# Acoustics_Board.net
KiCad netlist of a schematic drawn in Altium Designer
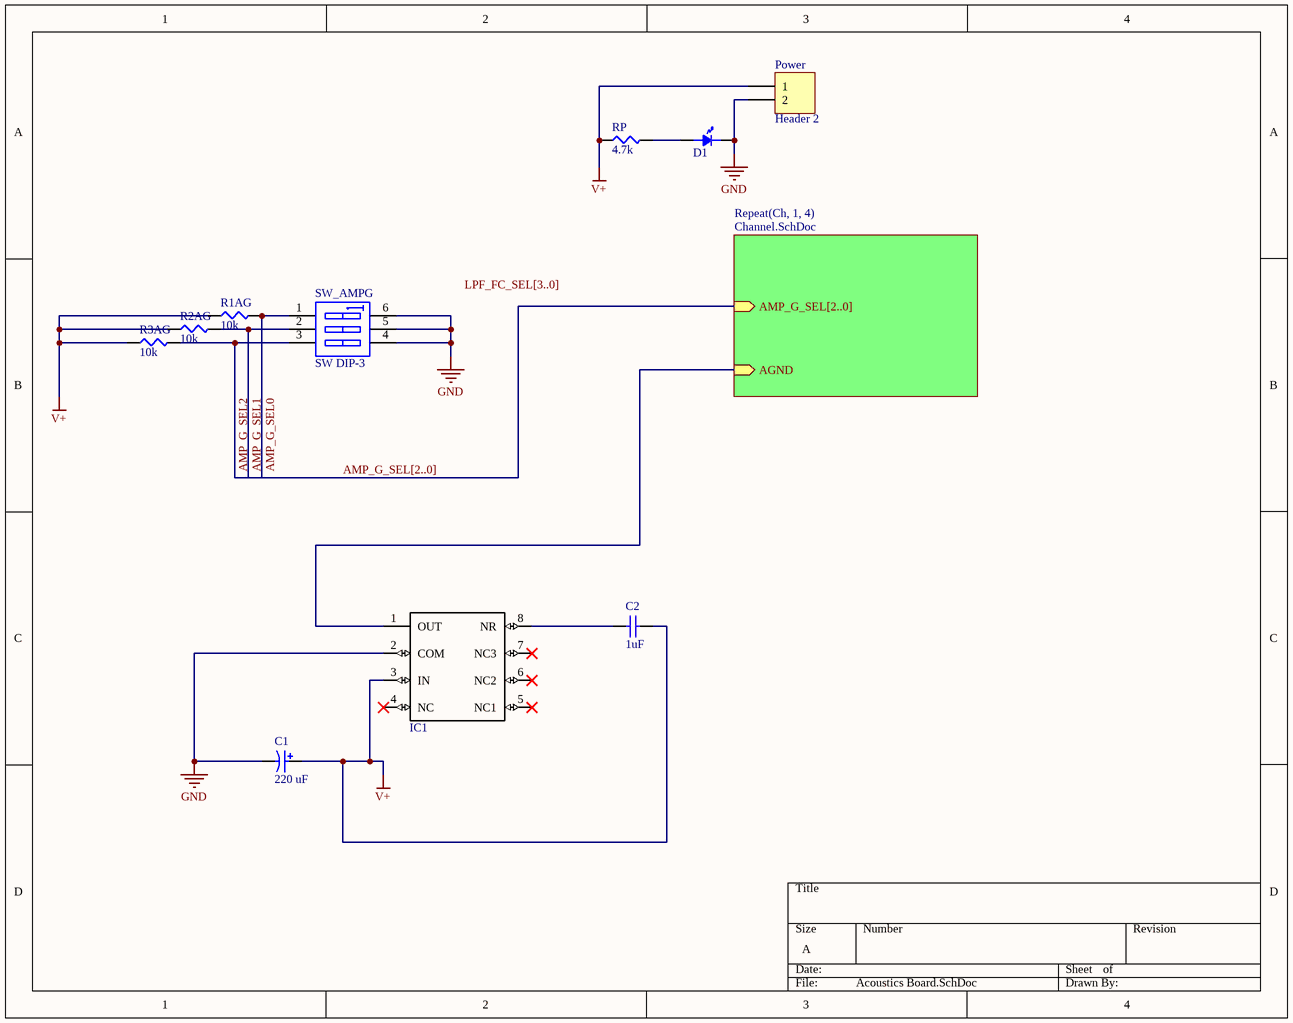
[diagram p0: Acoustics Board.SchDoc]

(export (version "E")
  (design (tool "Eeschema 10.0.6"))
  (components
    (comp (ref "C1")
      (value "220 uF")
      (footprint "PNSC-FK-V-H13_V")
      (fields (field (name "MANUFACTURER") "Panasonic"))
      (libsource (lib "Altium Content Vault") (part "CAP-P-2"))
    )
    (comp (ref "C2")
      (value "1uF")
      (footprint "C0805")
      (description "Unpolarized Capacitor")
      (fields (field (name "Comment") "Cap"))
      (libsource (lib "URC_Lib") (part "Cap"))
    )
    (comp (ref "D1") (value "LED") (footprint "LED0805") (libsource (lib "URC_Lib") (part "LED")))
    (comp (ref "IC1")
      (value "TLE2426")
      (footprint "SO8_M")
      (fields (field (name "MF") "Texas Instruments"))
      (libsource (lib "TLE2426") (part "TLE2426"))
    )
    (comp (ref "Power")
      (value "Header 2")
      (footprint "HDR1X2")
      (description "Header, 2-Pin")
      (fields (field (name "PUBLISHER") "Altium Limited"))
      (libsource (lib "Miscellaneous Connectors") (part "Header 2"))
    )
    (comp (ref "R1AG")
      (value "10k")
      (footprint "SMD-0805-RES")
      (description "RES SMD 10K OHM 1% 1/8W 0805")
      (fields
        (field (name "PART NUMBER") "ERJ-6ENF1002V")
        (field (name "DIGI-KEY PART NUMBER") "P10.0KCCT-ND")
      )
      (libsource (lib "Panasonic_ERJ_0805") (part "ERJ-6ENF1002V"))
    )
    (comp (ref "R2AG")
      (value "10k")
      (footprint "SMD-0805-RES")
      (description "RES SMD 10K OHM 1% 1/8W 0805")
      (fields
        (field (name "PART NUMBER") "ERJ-6ENF1002V")
        (field (name "DIGI-KEY PART NUMBER") "P10.0KCCT-ND")
      )
      (libsource (lib "Panasonic_ERJ_0805") (part "ERJ-6ENF1002V"))
    )
    (comp (ref "R3AG")
      (value "10k")
      (footprint "SMD-0805-RES")
      (description "RES SMD 10K OHM 1% 1/8W 0805")
      (fields
        (field (name "PART NUMBER") "ERJ-6ENF1002V")
        (field (name "DIGI-KEY PART NUMBER") "P10.0KCCT-ND")
      )
      (libsource (lib "Panasonic_ERJ_0805") (part "ERJ-6ENF1002V"))
    )
    (comp (ref "RP")
      (value "4.7k")
      (footprint "SMD-0805-RES")
      (description "RES SMD 10K OHM 1% 1/8W 0805")
      (fields
        (field (name "PART NUMBER") "ERJ-6ENF1002V")
        (field (name "DIGI-KEY PART NUMBER") "P10.0KCCT-ND")
      )
      (libsource (lib "Panasonic_ERJ_0805") (part "ERJ-6ENF1002V"))
    )
    (comp (ref "SW_AMPG")
      (value "SW DIP-3")
      (footprint "DIP-6")
      (description "DIP Switch, 3 Position, SPST")
      (fields (field (name "PUBLISHER") "Altium Limited"))
      (libsource (lib "Miscellaneous Devices") (part "SW DIP-3"))
    )
  )
  (nets
    (net (code "5") (name "/AGND") (class "Default")
      (node (ref "IC1") (pin "1") (pinfunction "OUT_1") (pintype "power_in"))
    )
    (net (code "6") (name "/AMP_G_SEL0") (class "Default")
      (node (ref "R1AG") (pin "2") (pinfunction "2_2") (pintype "passive"))
      (node (ref "SW_AMPG") (pin "1") (pinfunction "A1_1") (pintype "passive"))
    )
    (net (code "7") (name "/AMP_G_SEL1") (class "Default")
      (node (ref "R2AG") (pin "2") (pinfunction "2_2") (pintype "passive"))
      (node (ref "SW_AMPG") (pin "2") (pinfunction "A2_2") (pintype "passive"))
    )
    (net (code "8") (name "/AMP_G_SEL2") (class "Default")
      (node (ref "R3AG") (pin "2") (pinfunction "2_2") (pintype "passive"))
      (node (ref "SW_AMPG") (pin "3") (pinfunction "A3_3") (pintype "passive"))
    )
    (net (code "11") (name "GND") (class "Default")
      (node (ref "C1") (pin "2") (pinfunction "2_2") (pintype "passive"))
      (node (ref "D1") (pin "1") (pinfunction "1_1") (pintype "passive"))
      (node (ref "IC1") (pin "2") (pinfunction "COM_2") (pintype "bidirectional"))
      (node (ref "Power") (pin "2") (pinfunction "2_2") (pintype "passive"))
      (node (ref "SW_AMPG") (pin "4") (pinfunction "B3_4") (pintype "passive"))
      (node (ref "SW_AMPG") (pin "5") (pinfunction "B2_5") (pintype "passive"))
      (node (ref "SW_AMPG") (pin "6") (pinfunction "B1_6") (pintype "passive"))
    )
    (net (code "12") (name "Net-(D1-Pad2)") (class "Default")
      (node (ref "D1") (pin "2") (pinfunction "2_2") (pintype "passive"))
      (node (ref "RP") (pin "2") (pinfunction "2_2") (pintype "passive"))
    )
    (net (code "13") (name "Net-(IC1-NR)") (class "Default")
      (node (ref "C2") (pin "2") (pinfunction "2_2") (pintype "passive"))
      (node (ref "IC1") (pin "8") (pinfunction "NR_8") (pintype "bidirectional"))
    )
    (net (code "14") (name "V+") (class "Default")
      (node (ref "C1") (pin "1") (pinfunction "1_1") (pintype "passive"))
      (node (ref "C2") (pin "1") (pinfunction "1_1") (pintype "passive"))
      (node (ref "IC1") (pin "3") (pinfunction "IN_3") (pintype "bidirectional"))
      (node (ref "Power") (pin "1") (pinfunction "1_1") (pintype "passive"))
      (node (ref "R1AG") (pin "1") (pinfunction "1_1") (pintype "passive"))
      (node (ref "R2AG") (pin "1") (pinfunction "1_1") (pintype "passive"))
      (node (ref "R3AG") (pin "1") (pinfunction "1_1") (pintype "passive"))
      (node (ref "RP") (pin "1") (pinfunction "1_1") (pintype "passive"))
    )
    (net (code "15") (name "unconnected-(IC1-NC-Pad4)") (class "Default")
      (node (ref "IC1") (pin "4") (pinfunction "NC_4") (pintype "bidirectional+no_connect"))
    )
    (net (code "16") (name "unconnected-(IC1-NC1-Pad5)") (class "Default")
      (node (ref "IC1") (pin "5") (pinfunction "NC1_5") (pintype "bidirectional+no_connect"))
    )
    (net (code "17") (name "unconnected-(IC1-NC2-Pad6)") (class "Default")
      (node (ref "IC1") (pin "6") (pinfunction "NC2_6") (pintype "bidirectional+no_connect"))
    )
    (net (code "18") (name "unconnected-(IC1-NC3-Pad7)") (class "Default")
      (node (ref "IC1") (pin "7") (pinfunction "NC3_7") (pintype "bidirectional+no_connect"))
    )
  )
)
